# EmergencySwitch.net
KiCad netlist of a schematic drawn in EAGLE
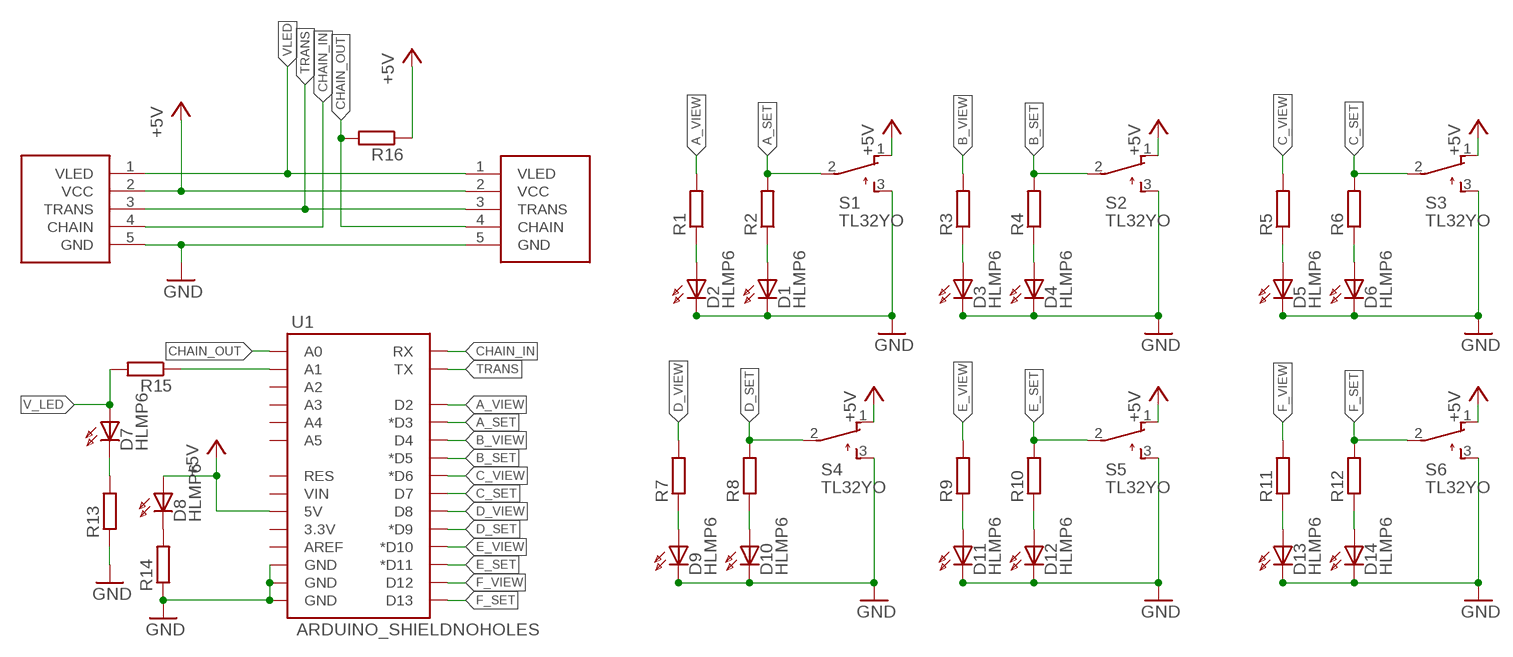
[diagram p0: schematic, sheet 1]

(export (version "E")
  (design (tool "Eeschema 10.0.6"))
  (components
    (comp (ref "CONN_IN")
      (value "SERIAL_SENSORXH")
      (footprint "eagle-import:XH-5")
      (libsource (lib "eagle-import") (part "SERIAL_SENSORXH"))
    )
    (comp (ref "CONN_OUT")
      (value "SERIAL_SENSORXH")
      (footprint "eagle-import:XH-5")
      (libsource (lib "eagle-import") (part "SERIAL_SENSORXH"))
    )
    (comp (ref "D1")
      (value "HLMP6")
      (footprint "eagle-import:HLMP6")
      (fields (field (name "MF") "AGILENT TECHNOLOGIES") (field (name "MPN") "HLMP-6500"))
      (libsource (lib "eagle-import") (part "HLMP6"))
    )
    (comp (ref "D2")
      (value "HLMP6")
      (footprint "eagle-import:HLMP6")
      (fields
        (field (name "MF") "AGILENT TECHNOLOGIES")
        (field (name "MPN") "HLMP-6500")
        (field (name "MF_1") "AGILENT TECHNOLOGIES")
        (field (name "MPN_1") "HLMP-6500")
        (field (name "OC_FARNELL") "1652490")
        (field (name "OC_NEWARK") "40K0088")
      )
      (libsource (lib "eagle-import") (part "HLMP6"))
    )
    (comp (ref "D3")
      (value "HLMP6")
      (footprint "eagle-import:HLMP6")
      (fields
        (field (name "MF") "AGILENT TECHNOLOGIES")
        (field (name "MPN") "HLMP-6500")
        (field (name "MF_1") "AGILENT TECHNOLOGIES")
        (field (name "MPN_1") "HLMP-6500")
        (field (name "OC_FARNELL") "1652490")
        (field (name "OC_NEWARK") "40K0088")
      )
      (libsource (lib "eagle-import") (part "HLMP6"))
    )
    (comp (ref "D4")
      (value "HLMP6")
      (footprint "eagle-import:HLMP6")
      (fields (field (name "MF") "AGILENT TECHNOLOGIES") (field (name "MPN") "HLMP-6500"))
      (libsource (lib "eagle-import") (part "HLMP6"))
    )
    (comp (ref "D5")
      (value "HLMP6")
      (footprint "eagle-import:HLMP6")
      (fields
        (field (name "MF") "AGILENT TECHNOLOGIES")
        (field (name "MPN") "HLMP-6500")
        (field (name "MF_1") "AGILENT TECHNOLOGIES")
        (field (name "MPN_1") "HLMP-6500")
        (field (name "OC_FARNELL") "1652490")
        (field (name "OC_NEWARK") "40K0088")
      )
      (libsource (lib "eagle-import") (part "HLMP6"))
    )
    (comp (ref "D6")
      (value "HLMP6")
      (footprint "eagle-import:HLMP6")
      (fields (field (name "MF") "AGILENT TECHNOLOGIES") (field (name "MPN") "HLMP-6500"))
      (libsource (lib "eagle-import") (part "HLMP6"))
    )
    (comp (ref "D7")
      (value "HLMP6")
      (footprint "eagle-import:HLMP6")
      (fields
        (field (name "MF") "AGILENT TECHNOLOGIES")
        (field (name "MPN") "HLMP-6500")
        (field (name "MF_1") "AGILENT TECHNOLOGIES")
        (field (name "MPN_1") "HLMP-6500")
        (field (name "OC_FARNELL") "1652490")
        (field (name "OC_NEWARK") "40K0088")
      )
      (libsource (lib "eagle-import") (part "HLMP6"))
    )
    (comp (ref "D8")
      (value "HLMP6")
      (footprint "eagle-import:HLMP6")
      (fields
        (field (name "MF") "AGILENT TECHNOLOGIES")
        (field (name "MPN") "HLMP-6500")
        (field (name "MF_1") "AGILENT TECHNOLOGIES")
        (field (name "MPN_1") "HLMP-6500")
        (field (name "OC_FARNELL") "1652490")
        (field (name "OC_NEWARK") "40K0088")
      )
      (libsource (lib "eagle-import") (part "HLMP6"))
    )
    (comp (ref "D9")
      (value "HLMP6")
      (footprint "eagle-import:HLMP6")
      (fields
        (field (name "MF") "AGILENT TECHNOLOGIES")
        (field (name "MPN") "HLMP-6500")
        (field (name "MF_1") "AGILENT TECHNOLOGIES")
        (field (name "MPN_1") "HLMP-6500")
        (field (name "OC_FARNELL") "1652490")
        (field (name "OC_NEWARK") "40K0088")
      )
      (libsource (lib "eagle-import") (part "HLMP6"))
    )
    (comp (ref "D10")
      (value "HLMP6")
      (footprint "eagle-import:HLMP6")
      (fields (field (name "MF") "AGILENT TECHNOLOGIES") (field (name "MPN") "HLMP-6500"))
      (libsource (lib "eagle-import") (part "HLMP6"))
    )
    (comp (ref "D11")
      (value "HLMP6")
      (footprint "eagle-import:HLMP6")
      (fields
        (field (name "MF") "AGILENT TECHNOLOGIES")
        (field (name "MPN") "HLMP-6500")
        (field (name "MF_1") "AGILENT TECHNOLOGIES")
        (field (name "MPN_1") "HLMP-6500")
        (field (name "OC_FARNELL") "1652490")
        (field (name "OC_NEWARK") "40K0088")
      )
      (libsource (lib "eagle-import") (part "HLMP6"))
    )
    (comp (ref "D12")
      (value "HLMP6")
      (footprint "eagle-import:HLMP6")
      (fields (field (name "MF") "AGILENT TECHNOLOGIES") (field (name "MPN") "HLMP-6500"))
      (libsource (lib "eagle-import") (part "HLMP6"))
    )
    (comp (ref "D13")
      (value "HLMP6")
      (footprint "eagle-import:HLMP6")
      (fields
        (field (name "MF") "AGILENT TECHNOLOGIES")
        (field (name "MPN") "HLMP-6500")
        (field (name "MF_1") "AGILENT TECHNOLOGIES")
        (field (name "MPN_1") "HLMP-6500")
        (field (name "OC_FARNELL") "1652490")
        (field (name "OC_NEWARK") "40K0088")
      )
      (libsource (lib "eagle-import") (part "HLMP6"))
    )
    (comp (ref "D14")
      (value "HLMP6")
      (footprint "eagle-import:HLMP6")
      (fields (field (name "MF") "AGILENT TECHNOLOGIES") (field (name "MPN") "HLMP-6500"))
      (libsource (lib "eagle-import") (part "HLMP6"))
    )
    (comp (ref "R1")
      (value "R-EU_R0603")
      (footprint "eagle-import:R0603")
      (libsource (lib "eagle-import") (part "R-EU_R0603"))
    )
    (comp (ref "R2")
      (value "R-EU_R0603")
      (footprint "eagle-import:R0603")
      (libsource (lib "eagle-import") (part "R-EU_R0603"))
    )
    (comp (ref "R3")
      (value "R-EU_R0603")
      (footprint "eagle-import:R0603")
      (libsource (lib "eagle-import") (part "R-EU_R0603"))
    )
    (comp (ref "R4")
      (value "R-EU_R0603")
      (footprint "eagle-import:R0603")
      (libsource (lib "eagle-import") (part "R-EU_R0603"))
    )
    (comp (ref "R5")
      (value "R-EU_R0603")
      (footprint "eagle-import:R0603")
      (libsource (lib "eagle-import") (part "R-EU_R0603"))
    )
    (comp (ref "R6")
      (value "R-EU_R0603")
      (footprint "eagle-import:R0603")
      (libsource (lib "eagle-import") (part "R-EU_R0603"))
    )
    (comp (ref "R7")
      (value "R-EU_R0603")
      (footprint "eagle-import:R0603")
      (libsource (lib "eagle-import") (part "R-EU_R0603"))
    )
    (comp (ref "R8")
      (value "R-EU_R0603")
      (footprint "eagle-import:R0603")
      (libsource (lib "eagle-import") (part "R-EU_R0603"))
    )
    (comp (ref "R9")
      (value "R-EU_R0603")
      (footprint "eagle-import:R0603")
      (libsource (lib "eagle-import") (part "R-EU_R0603"))
    )
    (comp (ref "R10")
      (value "R-EU_R0603")
      (footprint "eagle-import:R0603")
      (libsource (lib "eagle-import") (part "R-EU_R0603"))
    )
    (comp (ref "R11")
      (value "R-EU_R0603")
      (footprint "eagle-import:R0603")
      (libsource (lib "eagle-import") (part "R-EU_R0603"))
    )
    (comp (ref "R12")
      (value "R-EU_R0603")
      (footprint "eagle-import:R0603")
      (libsource (lib "eagle-import") (part "R-EU_R0603"))
    )
    (comp (ref "R13")
      (value "R-EU_R0603")
      (footprint "eagle-import:R0603")
      (libsource (lib "eagle-import") (part "R-EU_R0603"))
    )
    (comp (ref "R14")
      (value "R-EU_R0603")
      (footprint "eagle-import:R0603")
      (libsource (lib "eagle-import") (part "R-EU_R0603"))
    )
    (comp (ref "R15")
      (value "R-EU_R0603")
      (footprint "eagle-import:R0603")
      (libsource (lib "eagle-import") (part "R-EU_R0603"))
    )
    (comp (ref "R16")
      (value "R-EU_R0603")
      (footprint "eagle-import:R0603")
      (libsource (lib "eagle-import") (part "R-EU_R0603"))
    )
    (comp (ref "S1")
      (value "TL32YO")
      (footprint "eagle-import:TL3XYO")
      (libsource (lib "eagle-import") (part "TL32YO"))
    )
    (comp (ref "S2")
      (value "TL32YO")
      (footprint "eagle-import:TL3XYO")
      (libsource (lib "eagle-import") (part "TL32YO"))
    )
    (comp (ref "S3")
      (value "TL32YO")
      (footprint "eagle-import:TL3XYO")
      (libsource (lib "eagle-import") (part "TL32YO"))
    )
    (comp (ref "S4")
      (value "TL32YO")
      (footprint "eagle-import:TL3XYO")
      (libsource (lib "eagle-import") (part "TL32YO"))
    )
    (comp (ref "S5")
      (value "TL32YO")
      (footprint "eagle-import:TL3XYO")
      (libsource (lib "eagle-import") (part "TL32YO"))
    )
    (comp (ref "S6")
      (value "TL32YO")
      (footprint "eagle-import:TL3XYO")
      (libsource (lib "eagle-import") (part "TL32YO"))
    )
    (comp (ref "U1")
      (value "ARDUINO_SHIELDNOHOLES")
      (footprint "eagle-import:DUEMILANOVE_SHIELD_NOHOLES")
      (libsource (lib "eagle-import") (part "ARDUINO_SHIELDNOHOLES"))
    )
  )
  (nets
    (net (code "1") (name "+5V") (class "Default")
      (node (ref "CONN_IN") (pin "2") (pinfunction "VCC_2") (pintype "bidirectional"))
      (node (ref "CONN_OUT") (pin "2") (pinfunction "VCC_2") (pintype "bidirectional"))
      (node (ref "D8") (pin "A") (pinfunction "A_A") (pintype "passive"))
      (node (ref "R16") (pin "1") (pinfunction "1_1") (pintype "passive"))
      (node (ref "S1") (pin "1") (pinfunction "O_1") (pintype "passive"))
      (node (ref "S2") (pin "1") (pinfunction "O_1") (pintype "passive"))
      (node (ref "S3") (pin "1") (pinfunction "O_1") (pintype "passive"))
      (node (ref "S4") (pin "1") (pinfunction "O_1") (pintype "passive"))
      (node (ref "S5") (pin "1") (pinfunction "O_1") (pintype "passive"))
      (node (ref "S6") (pin "1") (pinfunction "O_1") (pintype "passive"))
      (node (ref "U1") (pin "5V") (pinfunction "5V_5V") (pintype "bidirectional"))
    )
    (net (code "2") (name "A_SET") (class "Default")
      (node (ref "R2") (pin "2") (pinfunction "2_2") (pintype "passive"))
      (node (ref "S1") (pin "2") (pinfunction "P_2") (pintype "passive"))
      (node (ref "U1") (pin "D3") (pinfunction "*D3_D3") (pintype "bidirectional"))
    )
    (net (code "3") (name "A_VIEW") (class "Default")
      (node (ref "R1") (pin "2") (pinfunction "2_2") (pintype "passive"))
      (node (ref "U1") (pin "D2") (pinfunction "D2_D2") (pintype "bidirectional"))
    )
    (net (code "4") (name "B_SET") (class "Default")
      (node (ref "R4") (pin "2") (pinfunction "2_2") (pintype "passive"))
      (node (ref "S2") (pin "2") (pinfunction "P_2") (pintype "passive"))
      (node (ref "U1") (pin "D5") (pinfunction "*D5_D5") (pintype "bidirectional"))
    )
    (net (code "5") (name "B_VIEW") (class "Default")
      (node (ref "R3") (pin "2") (pinfunction "2_2") (pintype "passive"))
      (node (ref "U1") (pin "D4") (pinfunction "D4_D4") (pintype "bidirectional"))
    )
    (net (code "6") (name "CHAIN_IN") (class "Default")
      (node (ref "CONN_IN") (pin "4") (pinfunction "CHAIN_4") (pintype "bidirectional"))
      (node (ref "U1") (pin "RX") (pinfunction "RX_RX") (pintype "bidirectional"))
    )
    (net (code "7") (name "CHAIN_OUT") (class "Default")
      (node (ref "CONN_OUT") (pin "4") (pinfunction "CHAIN_4") (pintype "bidirectional"))
      (node (ref "R16") (pin "2") (pinfunction "2_2") (pintype "passive"))
      (node (ref "U1") (pin "A0") (pinfunction "A0_A0") (pintype "bidirectional"))
    )
    (net (code "8") (name "C_SET") (class "Default")
      (node (ref "R6") (pin "2") (pinfunction "2_2") (pintype "passive"))
      (node (ref "S3") (pin "2") (pinfunction "P_2") (pintype "passive"))
      (node (ref "U1") (pin "D7") (pinfunction "D7_D7") (pintype "bidirectional"))
    )
    (net (code "9") (name "C_VIEW") (class "Default")
      (node (ref "R5") (pin "2") (pinfunction "2_2") (pintype "passive"))
      (node (ref "U1") (pin "D6") (pinfunction "*D6_D6") (pintype "bidirectional"))
    )
    (net (code "10") (name "D_SET") (class "Default")
      (node (ref "R8") (pin "2") (pinfunction "2_2") (pintype "passive"))
      (node (ref "S4") (pin "2") (pinfunction "P_2") (pintype "passive"))
      (node (ref "U1") (pin "D9") (pinfunction "*D9_D9") (pintype "bidirectional"))
    )
    (net (code "11") (name "D_VIEW") (class "Default")
      (node (ref "R7") (pin "2") (pinfunction "2_2") (pintype "passive"))
      (node (ref "U1") (pin "D8") (pinfunction "D8_D8") (pintype "bidirectional"))
    )
    (net (code "12") (name "E_SET") (class "Default")
      (node (ref "R10") (pin "2") (pinfunction "2_2") (pintype "passive"))
      (node (ref "S5") (pin "2") (pinfunction "P_2") (pintype "passive"))
      (node (ref "U1") (pin "D11") (pinfunction "*D11_D11") (pintype "bidirectional"))
    )
    (net (code "13") (name "E_VIEW") (class "Default")
      (node (ref "R9") (pin "2") (pinfunction "2_2") (pintype "passive"))
      (node (ref "U1") (pin "D10") (pinfunction "*D10_D10") (pintype "bidirectional"))
    )
    (net (code "14") (name "F_SET") (class "Default")
      (node (ref "R12") (pin "2") (pinfunction "2_2") (pintype "passive"))
      (node (ref "S6") (pin "2") (pinfunction "P_2") (pintype "passive"))
      (node (ref "U1") (pin "D13") (pinfunction "D13_D13") (pintype "bidirectional"))
    )
    (net (code "15") (name "F_VIEW") (class "Default")
      (node (ref "R11") (pin "2") (pinfunction "2_2") (pintype "passive"))
      (node (ref "U1") (pin "D12") (pinfunction "D12_D12") (pintype "bidirectional"))
    )
    (net (code "16") (name "GND") (class "Default")
      (node (ref "CONN_IN") (pin "5") (pinfunction "GND_5") (pintype "bidirectional"))
      (node (ref "CONN_OUT") (pin "5") (pinfunction "GND_5") (pintype "bidirectional"))
      (node (ref "D1") (pin "K") (pinfunction "K_K") (pintype "passive"))
      (node (ref "D10") (pin "K") (pinfunction "K_K") (pintype "passive"))
      (node (ref "D11") (pin "K") (pinfunction "K_K") (pintype "passive"))
      (node (ref "D12") (pin "K") (pinfunction "K_K") (pintype "passive"))
      (node (ref "D13") (pin "K") (pinfunction "K_K") (pintype "passive"))
      (node (ref "D14") (pin "K") (pinfunction "K_K") (pintype "passive"))
      (node (ref "D2") (pin "K") (pinfunction "K_K") (pintype "passive"))
      (node (ref "D3") (pin "K") (pinfunction "K_K") (pintype "passive"))
      (node (ref "D4") (pin "K") (pinfunction "K_K") (pintype "passive"))
      (node (ref "D5") (pin "K") (pinfunction "K_K") (pintype "passive"))
      (node (ref "D6") (pin "K") (pinfunction "K_K") (pintype "passive"))
      (node (ref "D9") (pin "K") (pinfunction "K_K") (pintype "passive"))
      (node (ref "R13") (pin "1") (pinfunction "1_1") (pintype "passive"))
      (node (ref "R14") (pin "1") (pinfunction "1_1") (pintype "passive"))
      (node (ref "S1") (pin "3") (pinfunction "S_3") (pintype "passive"))
      (node (ref "S2") (pin "3") (pinfunction "S_3") (pintype "passive"))
      (node (ref "S3") (pin "3") (pinfunction "S_3") (pintype "passive"))
      (node (ref "S4") (pin "3") (pinfunction "S_3") (pintype "passive"))
      (node (ref "S5") (pin "3") (pinfunction "S_3") (pintype "passive"))
      (node (ref "S6") (pin "3") (pinfunction "S_3") (pintype "passive"))
      (node (ref "U1") (pin "GND@0") (pinfunction "GND_GND@0") (pintype "bidirectional"))
      (node (ref "U1") (pin "GND@1") (pinfunction "GND_GND@1") (pintype "bidirectional"))
      (node (ref "U1") (pin "GND@2") (pinfunction "GND_GND@2") (pintype "bidirectional"))
    )
    (net (code "17") (name "Net-(D1-PadA)") (class "Default")
      (node (ref "D1") (pin "A") (pinfunction "A_A") (pintype "passive"))
      (node (ref "R2") (pin "1") (pinfunction "1_1") (pintype "passive"))
    )
    (net (code "18") (name "Net-(D2-PadA)") (class "Default")
      (node (ref "D2") (pin "A") (pinfunction "A_A") (pintype "passive"))
      (node (ref "R1") (pin "1") (pinfunction "1_1") (pintype "passive"))
    )
    (net (code "19") (name "Net-(D3-PadA)") (class "Default")
      (node (ref "D3") (pin "A") (pinfunction "A_A") (pintype "passive"))
      (node (ref "R3") (pin "1") (pinfunction "1_1") (pintype "passive"))
    )
    (net (code "20") (name "Net-(D4-PadA)") (class "Default")
      (node (ref "D4") (pin "A") (pinfunction "A_A") (pintype "passive"))
      (node (ref "R4") (pin "1") (pinfunction "1_1") (pintype "passive"))
    )
    (net (code "21") (name "Net-(D5-PadA)") (class "Default")
      (node (ref "D5") (pin "A") (pinfunction "A_A") (pintype "passive"))
      (node (ref "R5") (pin "1") (pinfunction "1_1") (pintype "passive"))
    )
    (net (code "22") (name "Net-(D6-PadA)") (class "Default")
      (node (ref "D6") (pin "A") (pinfunction "A_A") (pintype "passive"))
      (node (ref "R6") (pin "1") (pinfunction "1_1") (pintype "passive"))
    )
    (net (code "23") (name "Net-(D7-PadK)") (class "Default")
      (node (ref "D7") (pin "K") (pinfunction "K_K") (pintype "passive"))
      (node (ref "R13") (pin "2") (pinfunction "2_2") (pintype "passive"))
    )
    (net (code "24") (name "Net-(D8-PadK)") (class "Default")
      (node (ref "D8") (pin "K") (pinfunction "K_K") (pintype "passive"))
      (node (ref "R14") (pin "2") (pinfunction "2_2") (pintype "passive"))
    )
    (net (code "25") (name "Net-(D9-PadA)") (class "Default")
      (node (ref "D9") (pin "A") (pinfunction "A_A") (pintype "passive"))
      (node (ref "R7") (pin "1") (pinfunction "1_1") (pintype "passive"))
    )
    (net (code "26") (name "Net-(D10-PadA)") (class "Default")
      (node (ref "D10") (pin "A") (pinfunction "A_A") (pintype "passive"))
      (node (ref "R8") (pin "1") (pinfunction "1_1") (pintype "passive"))
    )
    (net (code "27") (name "Net-(D11-PadA)") (class "Default")
      (node (ref "D11") (pin "A") (pinfunction "A_A") (pintype "passive"))
      (node (ref "R9") (pin "1") (pinfunction "1_1") (pintype "passive"))
    )
    (net (code "28") (name "Net-(D12-PadA)") (class "Default")
      (node (ref "D12") (pin "A") (pinfunction "A_A") (pintype "passive"))
      (node (ref "R10") (pin "1") (pinfunction "1_1") (pintype "passive"))
    )
    (net (code "29") (name "Net-(D13-PadA)") (class "Default")
      (node (ref "D13") (pin "A") (pinfunction "A_A") (pintype "passive"))
      (node (ref "R11") (pin "1") (pinfunction "1_1") (pintype "passive"))
    )
    (net (code "30") (name "Net-(D14-PadA)") (class "Default")
      (node (ref "D14") (pin "A") (pinfunction "A_A") (pintype "passive"))
      (node (ref "R12") (pin "1") (pinfunction "1_1") (pintype "passive"))
    )
    (net (code "31") (name "Net-(R15-Pad1)") (class "Default")
      (node (ref "R15") (pin "1") (pinfunction "1_1") (pintype "passive"))
      (node (ref "U1") (pin "A1") (pinfunction "A1_A1") (pintype "bidirectional"))
    )
    (net (code "32") (name "TRANS") (class "Default")
      (node (ref "CONN_IN") (pin "3") (pinfunction "TRANS_3") (pintype "bidirectional"))
      (node (ref "CONN_OUT") (pin "3") (pinfunction "TRANS_3") (pintype "bidirectional"))
      (node (ref "U1") (pin "TX") (pinfunction "TX_TX") (pintype "bidirectional"))
    )
    (net (code "33") (name "VLED") (class "Default")
      (node (ref "CONN_IN") (pin "1") (pinfunction "VLED_1") (pintype "bidirectional"))
      (node (ref "CONN_OUT") (pin "1") (pinfunction "VLED_1") (pintype "bidirectional"))
    )
    (net (code "34") (name "V_LED") (class "Default")
      (node (ref "D7") (pin "A") (pinfunction "A_A") (pintype "passive"))
      (node (ref "R15") (pin "2") (pinfunction "2_2") (pintype "passive"))
    )
    (net (code "35") (name "unconnected-(U1-Pad3.3V)") (class "Default")
      (node (ref "U1") (pin "3.3V") (pinfunction "3.3V_3.3V") (pintype "bidirectional"))
    )
    (net (code "36") (name "unconnected-(U1-PadA2)") (class "Default")
      (node (ref "U1") (pin "A2") (pinfunction "A2_A2") (pintype "bidirectional"))
    )
    (net (code "37") (name "unconnected-(U1-PadA3)") (class "Default")
      (node (ref "U1") (pin "A3") (pinfunction "A3_A3") (pintype "bidirectional"))
    )
    (net (code "38") (name "unconnected-(U1-PadA4)") (class "Default")
      (node (ref "U1") (pin "A4") (pinfunction "A4_A4") (pintype "bidirectional"))
    )
    (net (code "39") (name "unconnected-(U1-PadA5)") (class "Default")
      (node (ref "U1") (pin "A5") (pinfunction "A5_A5") (pintype "bidirectional"))
    )
    (net (code "40") (name "unconnected-(U1-PadAREF)") (class "Default")
      (node (ref "U1") (pin "AREF") (pinfunction "AREF_AREF") (pintype "bidirectional"))
    )
    (net (code "41") (name "unconnected-(U1-PadRES)") (class "Default")
      (node (ref "U1") (pin "RES") (pinfunction "RES_RES") (pintype "bidirectional"))
    )
    (net (code "42") (name "unconnected-(U1-PadVIN)") (class "Default")
      (node (ref "U1") (pin "VIN") (pinfunction "VIN_VIN") (pintype "bidirectional"))
    )
  )
)
